# SENSOR.net
KiCad netlist of a schematic drawn in EAGLE
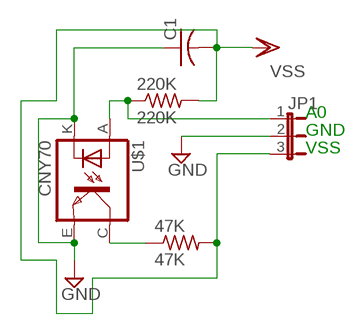
[diagram p0: schematic, sheet 1]

(export (version "E")
  (design (tool "Eeschema 10.0.6"))
  (components
    (comp (ref "47K")
      (value "47K")
      (footprint "eagle-import:0309_12")
      (libsource (lib "eagle-import") (part "R-US_0309/12"))
    )
    (comp (ref "220K")
      (value "220K")
      (footprint "eagle-import:0309_12")
      (libsource (lib "eagle-import") (part "R-US_0309/12"))
    )
    (comp (ref "C1")
      (value "C-US025-030X050")
      (footprint "eagle-import:C025-030X050")
      (libsource (lib "eagle-import") (part "C-US025-030X050"))
    )
    (comp (ref "JP1")
      (value "JP2E")
      (footprint "eagle-import:JP2")
      (libsource (lib "eagle-import") (part "JP2E"))
    )
    (comp (ref "U$1")
      (value "CNY70")
      (footprint "eagle-import:4")
      (libsource (lib "eagle-import") (part "CNY70"))
    )
  )
  (nets
    (net (code "1") (name "GND") (class "Default")
      (node (ref "C1") (pin "1") (pinfunction "1_1") (pintype "passive"))
      (node (ref "JP1") (pin "2") (pinfunction "2_2") (pintype "passive"))
      (node (ref "U$1") (pin "E") (pinfunction "EMI_E") (pintype "passive"))
      (node (ref "U$1") (pin "K") (pinfunction "C_K") (pintype "passive"))
    )
    (net (code "2") (name "Net-(220K-Pad1)") (class "Default")
      (node (ref "220K") (pin "1") (pinfunction "1_1") (pintype "passive"))
      (node (ref "JP1") (pin "1") (pinfunction "1_1") (pintype "passive"))
      (node (ref "U$1") (pin "A") (pinfunction "A_A") (pintype "passive"))
    )
    (net (code "3") (name "Net-(U$1-COL)") (class "Default")
      (node (ref "47K") (pin "1") (pinfunction "1_1") (pintype "passive"))
      (node (ref "U$1") (pin "C") (pinfunction "COL_C") (pintype "passive"))
    )
    (net (code "4") (name "VSS") (class "Default")
      (node (ref "220K") (pin "2") (pinfunction "2_2") (pintype "passive"))
      (node (ref "47K") (pin "2") (pinfunction "2_2") (pintype "passive"))
      (node (ref "C1") (pin "2") (pinfunction "2_2") (pintype "passive"))
      (node (ref "JP1") (pin "3") (pinfunction "3_3") (pintype "passive"))
    )
  )
)
